# PonyProg_ver1.net
KiCad netlist of a schematic drawn in EAGLE
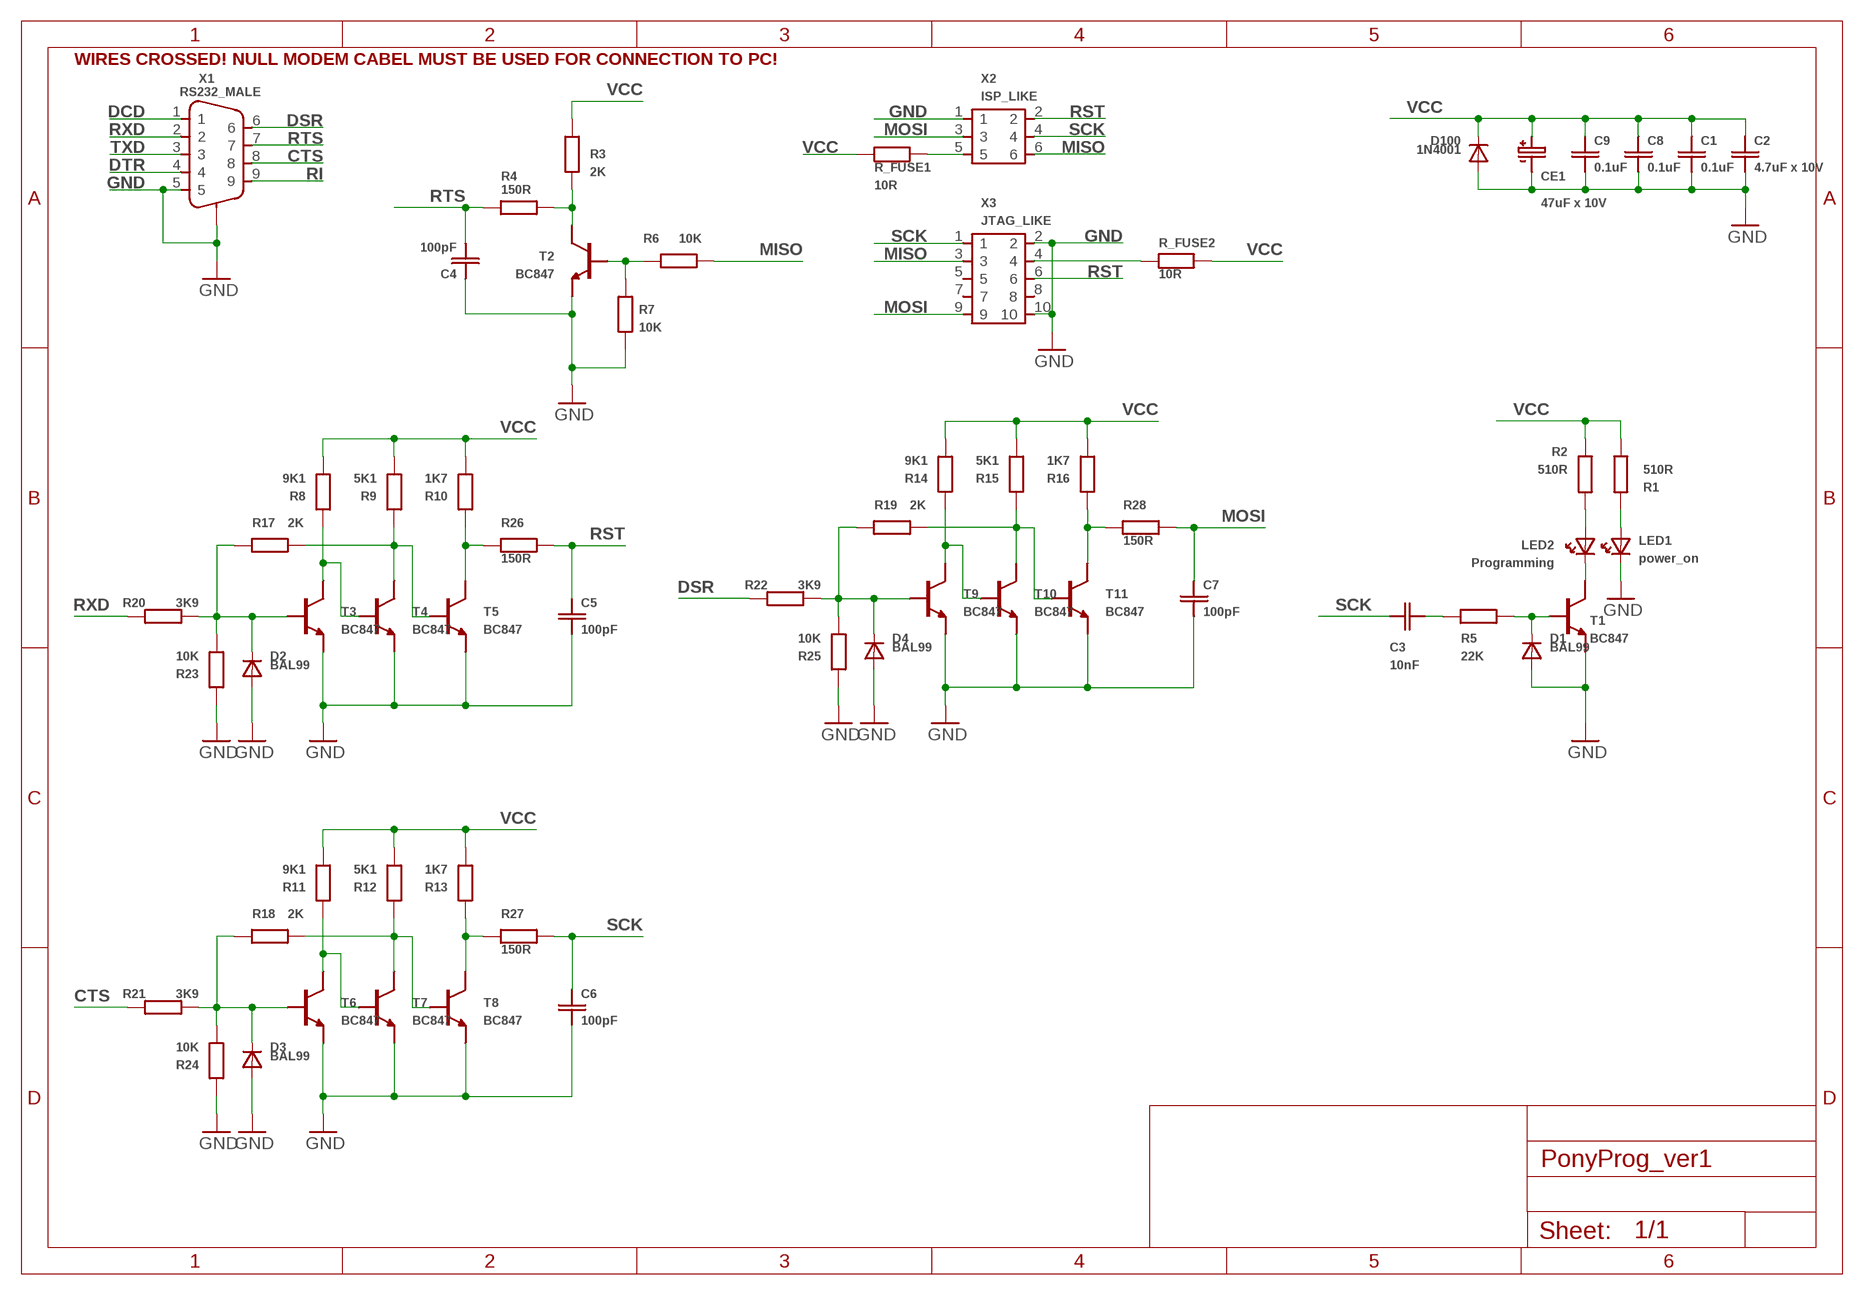
[diagram p0: schematic, sheet 1]

(export (version "E")
  (design (tool "Eeschema 10.0.6"))
  (components
    (comp (ref "C1")
      (value "0.1uF")
      (footprint "eagle-import:RSMD_0805")
      (libsource (lib "eagle-import") (part "CSMD_0805"))
    )
    (comp (ref "C2")
      (value "4.7uF x 10V")
      (footprint "eagle-import:RSMD_1206")
      (libsource (lib "eagle-import") (part "CSMD_1206"))
    )
    (comp (ref "C3")
      (value "10nF")
      (footprint "eagle-import:RSMD_0805")
      (libsource (lib "eagle-import") (part "CSMD_0805"))
    )
    (comp (ref "C4")
      (value "100pF")
      (footprint "eagle-import:RSMD_0805")
      (libsource (lib "eagle-import") (part "CSMD_0805"))
    )
    (comp (ref "C5")
      (value "100pF")
      (footprint "eagle-import:RSMD_0805")
      (libsource (lib "eagle-import") (part "CSMD_0805"))
    )
    (comp (ref "C6")
      (value "100pF")
      (footprint "eagle-import:RSMD_0805")
      (libsource (lib "eagle-import") (part "CSMD_0805"))
    )
    (comp (ref "C7")
      (value "100pF")
      (footprint "eagle-import:RSMD_0805")
      (libsource (lib "eagle-import") (part "CSMD_0805"))
    )
    (comp (ref "C8")
      (value "0.1uF")
      (footprint "eagle-import:RSMD_0805")
      (libsource (lib "eagle-import") (part "CSMD_0805"))
    )
    (comp (ref "C9")
      (value "0.1uF")
      (footprint "eagle-import:RSMD_0805")
      (libsource (lib "eagle-import") (part "CSMD_0805"))
    )
    (comp (ref "CE1")
      (value "47uF x 10V")
      (footprint "eagle-import:CE_6.3MM")
      (libsource (lib "eagle-import") (part "CE6.3MM"))
    )
    (comp (ref "D1")
      (value "BAL99")
      (footprint "eagle-import:SOT23_SMALL_PADS")
      (libsource (lib "eagle-import") (part "BAL99SOT23_SMALL_PADS"))
    )
    (comp (ref "D2")
      (value "BAL99")
      (footprint "eagle-import:SOT23_SMALL_PADS")
      (libsource (lib "eagle-import") (part "BAL99SOT23_SMALL_PADS"))
    )
    (comp (ref "D3")
      (value "BAL99")
      (footprint "eagle-import:SOT23_SMALL_PADS")
      (libsource (lib "eagle-import") (part "BAL99SOT23_SMALL_PADS"))
    )
    (comp (ref "D4")
      (value "BAL99")
      (footprint "eagle-import:SOT23_SMALL_PADS")
      (libsource (lib "eagle-import") (part "BAL99SOT23_SMALL_PADS"))
    )
    (comp (ref "D100")
      (value "1N4001")
      (footprint "eagle-import:DO-41_20MM")
      (libsource (lib "eagle-import") (part "1N4001DO-41_20MM"))
    )
    (comp (ref "LED1")
      (value "power_on")
      (footprint "eagle-import:LED3MM")
      (libsource (lib "eagle-import") (part "LED3MM"))
    )
    (comp (ref "LED2")
      (value "Programming")
      (footprint "eagle-import:LED3MM")
      (libsource (lib "eagle-import") (part "LED3MM"))
    )
    (comp (ref "R1")
      (value "510R")
      (footprint "eagle-import:RSMD_0805")
      (libsource (lib "eagle-import") (part "RSMD_0805"))
    )
    (comp (ref "R2")
      (value "510R")
      (footprint "eagle-import:RSMD_0805")
      (libsource (lib "eagle-import") (part "RSMD_0805"))
    )
    (comp (ref "R3")
      (value "2K")
      (footprint "eagle-import:RSMD_1206")
      (libsource (lib "eagle-import") (part "RSMD_1206"))
    )
    (comp (ref "R4")
      (value "150R")
      (footprint "eagle-import:RSMD_0805")
      (libsource (lib "eagle-import") (part "RSMD_0805"))
    )
    (comp (ref "R5")
      (value "22K")
      (footprint "eagle-import:RSMD_0805")
      (libsource (lib "eagle-import") (part "RSMD_0805"))
    )
    (comp (ref "R6")
      (value "10K")
      (footprint "eagle-import:RSMD_1206")
      (libsource (lib "eagle-import") (part "RSMD_1206"))
    )
    (comp (ref "R7")
      (value "10K")
      (footprint "eagle-import:RSMD_0805")
      (libsource (lib "eagle-import") (part "RSMD_0805"))
    )
    (comp (ref "R8")
      (value "9K1")
      (footprint "eagle-import:RSMD_1206")
      (libsource (lib "eagle-import") (part "RSMD_1206"))
    )
    (comp (ref "R9")
      (value "5K1")
      (footprint "eagle-import:RSMD_0805")
      (libsource (lib "eagle-import") (part "RSMD_0805"))
    )
    (comp (ref "R10")
      (value "1K7")
      (footprint "eagle-import:RSMD_0805")
      (libsource (lib "eagle-import") (part "RSMD_0805"))
    )
    (comp (ref "R11")
      (value "9K1")
      (footprint "eagle-import:RSMD_1206")
      (libsource (lib "eagle-import") (part "RSMD_1206"))
    )
    (comp (ref "R12")
      (value "5K1")
      (footprint "eagle-import:RSMD_0805")
      (libsource (lib "eagle-import") (part "RSMD_0805"))
    )
    (comp (ref "R13")
      (value "1K7")
      (footprint "eagle-import:RSMD_0805")
      (libsource (lib "eagle-import") (part "RSMD_0805"))
    )
    (comp (ref "R14")
      (value "9K1")
      (footprint "eagle-import:RSMD_1206")
      (libsource (lib "eagle-import") (part "RSMD_1206"))
    )
    (comp (ref "R15")
      (value "5K1")
      (footprint "eagle-import:RSMD_0805")
      (libsource (lib "eagle-import") (part "RSMD_0805"))
    )
    (comp (ref "R16")
      (value "1K7")
      (footprint "eagle-import:RSMD_0805")
      (libsource (lib "eagle-import") (part "RSMD_0805"))
    )
    (comp (ref "R17")
      (value "2K")
      (footprint "eagle-import:RSMD_0805")
      (libsource (lib "eagle-import") (part "RSMD_0805"))
    )
    (comp (ref "R18")
      (value "2K")
      (footprint "eagle-import:RSMD_0805")
      (libsource (lib "eagle-import") (part "RSMD_0805"))
    )
    (comp (ref "R19")
      (value "2K")
      (footprint "eagle-import:RSMD_0805")
      (libsource (lib "eagle-import") (part "RSMD_0805"))
    )
    (comp (ref "R20")
      (value "3K9")
      (footprint "eagle-import:RSMD_0805")
      (libsource (lib "eagle-import") (part "RSMD_0805"))
    )
    (comp (ref "R21")
      (value "3K9")
      (footprint "eagle-import:RSMD_0805")
      (libsource (lib "eagle-import") (part "RSMD_0805"))
    )
    (comp (ref "R22")
      (value "3K9")
      (footprint "eagle-import:RSMD_0805")
      (libsource (lib "eagle-import") (part "RSMD_0805"))
    )
    (comp (ref "R23")
      (value "10K")
      (footprint "eagle-import:RSMD_0805")
      (libsource (lib "eagle-import") (part "RSMD_0805"))
    )
    (comp (ref "R24")
      (value "10K")
      (footprint "eagle-import:RSMD_0805")
      (libsource (lib "eagle-import") (part "RSMD_0805"))
    )
    (comp (ref "R25")
      (value "10K")
      (footprint "eagle-import:RSMD_0805")
      (libsource (lib "eagle-import") (part "RSMD_0805"))
    )
    (comp (ref "R26")
      (value "150R")
      (footprint "eagle-import:RSMD_0805")
      (libsource (lib "eagle-import") (part "RSMD_0805"))
    )
    (comp (ref "R27")
      (value "150R")
      (footprint "eagle-import:RSMD_0805")
      (libsource (lib "eagle-import") (part "RSMD_0805"))
    )
    (comp (ref "R28")
      (value "150R")
      (footprint "eagle-import:RSMD_0805")
      (libsource (lib "eagle-import") (part "RSMD_0805"))
    )
    (comp (ref "R_FUSE1")
      (value "10R")
      (footprint "eagle-import:R0207")
      (libsource (lib "eagle-import") (part "R0207"))
    )
    (comp (ref "R_FUSE2")
      (value "10R")
      (footprint "eagle-import:R0207")
      (libsource (lib "eagle-import") (part "R0207"))
    )
    (comp (ref "T1")
      (value "BC847")
      (footprint "eagle-import:SOT23_SMALL_PADS")
      (libsource (lib "eagle-import") (part "BC847SOT23_SMALL_PADS"))
    )
    (comp (ref "T2")
      (value "BC847")
      (footprint "eagle-import:SOT23_SMALL_PADS")
      (libsource (lib "eagle-import") (part "BC847SOT23_SMALL_PADS"))
    )
    (comp (ref "T3")
      (value "BC847")
      (footprint "eagle-import:SOT23_SMALL_PADS")
      (libsource (lib "eagle-import") (part "BC847SOT23_SMALL_PADS"))
    )
    (comp (ref "T4")
      (value "BC847")
      (footprint "eagle-import:SOT23_SMALL_PADS")
      (libsource (lib "eagle-import") (part "BC847SOT23_SMALL_PADS"))
    )
    (comp (ref "T5")
      (value "BC847")
      (footprint "eagle-import:SOT23_SMALL_PADS")
      (libsource (lib "eagle-import") (part "BC847SOT23_SMALL_PADS"))
    )
    (comp (ref "T6")
      (value "BC847")
      (footprint "eagle-import:SOT23_SMALL_PADS")
      (libsource (lib "eagle-import") (part "BC847SOT23_SMALL_PADS"))
    )
    (comp (ref "T7")
      (value "BC847")
      (footprint "eagle-import:SOT23_SMALL_PADS")
      (libsource (lib "eagle-import") (part "BC847SOT23_SMALL_PADS"))
    )
    (comp (ref "T8")
      (value "BC847")
      (footprint "eagle-import:SOT23_SMALL_PADS")
      (libsource (lib "eagle-import") (part "BC847SOT23_SMALL_PADS"))
    )
    (comp (ref "T9")
      (value "BC847")
      (footprint "eagle-import:SOT23_SMALL_PADS")
      (libsource (lib "eagle-import") (part "BC847SOT23_SMALL_PADS"))
    )
    (comp (ref "T10")
      (value "BC847")
      (footprint "eagle-import:SOT23_SMALL_PADS")
      (libsource (lib "eagle-import") (part "BC847SOT23_SMALL_PADS"))
    )
    (comp (ref "T11")
      (value "BC847")
      (footprint "eagle-import:SOT23_SMALL_PADS")
      (libsource (lib "eagle-import") (part "BC847SOT23_SMALL_PADS"))
    )
    (comp (ref "X1")
      (value "RS232_MALE")
      (footprint "eagle-import:DSUB9_RA_MALE")
      (libsource (lib "eagle-import") (part "DSUB9_MALE"))
    )
    (comp (ref "X2")
      (value "ISP_LIKE")
      (footprint "eagle-import:PIN2X3_2.54MM")
      (libsource (lib "eagle-import") (part "PIN2X3_2.54MM"))
    )
    (comp (ref "X3")
      (value "JTAG_LIKE")
      (footprint "eagle-import:PIN2X5_2.54MM")
      (libsource (lib "eagle-import") (part "PIN2X5_2.54MM"))
    )
  )
  (nets
    (net (code "1") (name "/CTS") (class "Default")
      (node (ref "R21") (pin "PAD_1") (pinfunction "PIN1_PAD_1") (pintype "passive"))
      (node (ref "X1") (pin "8") (pinfunction "8_8") (pintype "bidirectional"))
    )
    (net (code "2") (name "/DCD") (class "Default")
      (node (ref "X1") (pin "1") (pinfunction "1_1") (pintype "bidirectional"))
    )
    (net (code "3") (name "/DSR") (class "Default")
      (node (ref "R22") (pin "PAD_1") (pinfunction "PIN1_PAD_1") (pintype "passive"))
      (node (ref "X1") (pin "6") (pinfunction "6_6") (pintype "bidirectional"))
    )
    (net (code "4") (name "/DTR") (class "Default")
      (node (ref "X1") (pin "4") (pinfunction "4_4") (pintype "bidirectional"))
    )
    (net (code "5") (name "/MISO") (class "Default")
      (node (ref "R6") (pin "PAD_1") (pinfunction "PIN1_PAD_1") (pintype "passive"))
      (node (ref "X2") (pin "6") (pinfunction "6_6") (pintype "bidirectional"))
      (node (ref "X3") (pin "3") (pinfunction "3_3") (pintype "bidirectional"))
    )
    (net (code "6") (name "/MOSI") (class "Default")
      (node (ref "C7") (pin "PAD_1") (pinfunction "PIN1_PAD_1") (pintype "bidirectional"))
      (node (ref "R28") (pin "PAD_0") (pinfunction "PIN0_PAD_0") (pintype "passive"))
      (node (ref "X2") (pin "3") (pinfunction "3_3") (pintype "bidirectional"))
      (node (ref "X3") (pin "9") (pinfunction "9_9") (pintype "bidirectional"))
    )
    (net (code "7") (name "/RI") (class "Default")
      (node (ref "X1") (pin "9") (pinfunction "9_9") (pintype "bidirectional"))
    )
    (net (code "8") (name "/RST") (class "Default")
      (node (ref "C5") (pin "PAD_1") (pinfunction "PIN1_PAD_1") (pintype "bidirectional"))
      (node (ref "R26") (pin "PAD_0") (pinfunction "PIN0_PAD_0") (pintype "passive"))
      (node (ref "X2") (pin "2") (pinfunction "2_2") (pintype "bidirectional"))
      (node (ref "X3") (pin "6") (pinfunction "6_6") (pintype "bidirectional"))
    )
    (net (code "9") (name "/RTS") (class "Default")
      (node (ref "C4") (pin "PAD_0") (pinfunction "PIN0_PAD_0") (pintype "bidirectional"))
      (node (ref "R4") (pin "PAD_1") (pinfunction "PIN1_PAD_1") (pintype "passive"))
      (node (ref "X1") (pin "7") (pinfunction "7_7") (pintype "bidirectional"))
    )
    (net (code "10") (name "/RXD") (class "Default")
      (node (ref "R20") (pin "PAD_1") (pinfunction "PIN1_PAD_1") (pintype "passive"))
      (node (ref "X1") (pin "2") (pinfunction "2_2") (pintype "bidirectional"))
    )
    (net (code "11") (name "/SCK") (class "Default")
      (node (ref "C3") (pin "PAD_1") (pinfunction "PIN1_PAD_1") (pintype "bidirectional"))
      (node (ref "C6") (pin "PAD_1") (pinfunction "PIN1_PAD_1") (pintype "bidirectional"))
      (node (ref "R27") (pin "PAD_0") (pinfunction "PIN0_PAD_0") (pintype "passive"))
      (node (ref "X2") (pin "4") (pinfunction "4_4") (pintype "bidirectional"))
      (node (ref "X3") (pin "1") (pinfunction "1_1") (pintype "bidirectional"))
    )
    (net (code "12") (name "/TXD") (class "Default")
      (node (ref "X1") (pin "3") (pinfunction "3_3") (pintype "bidirectional"))
    )
    (net (code "13") (name "/VCC") (class "Default")
      (node (ref "C1") (pin "PAD_1") (pinfunction "PIN1_PAD_1") (pintype "bidirectional"))
      (node (ref "C2") (pin "PAD_1") (pinfunction "PIN1_PAD_1") (pintype "bidirectional"))
      (node (ref "C8") (pin "PAD_1") (pinfunction "PIN1_PAD_1") (pintype "bidirectional"))
      (node (ref "C9") (pin "PAD_1") (pinfunction "PIN1_PAD_1") (pintype "bidirectional"))
      (node (ref "CE1") (pin "+") (pinfunction "+_+") (pintype "bidirectional"))
      (node (ref "D100") (pin "CATHODE") (pinfunction "CATHODE_CATHODE") (pintype "passive"))
      (node (ref "R1") (pin "PAD_0") (pinfunction "PIN0_PAD_0") (pintype "passive"))
      (node (ref "R10") (pin "PAD_0") (pinfunction "PIN0_PAD_0") (pintype "passive"))
      (node (ref "R11") (pin "PAD_0") (pinfunction "PIN0_PAD_0") (pintype "passive"))
      (node (ref "R12") (pin "PAD_0") (pinfunction "PIN0_PAD_0") (pintype "passive"))
      (node (ref "R13") (pin "PAD_0") (pinfunction "PIN0_PAD_0") (pintype "passive"))
      (node (ref "R14") (pin "PAD_0") (pinfunction "PIN0_PAD_0") (pintype "passive"))
      (node (ref "R15") (pin "PAD_0") (pinfunction "PIN0_PAD_0") (pintype "passive"))
      (node (ref "R16") (pin "PAD_0") (pinfunction "PIN0_PAD_0") (pintype "passive"))
      (node (ref "R2") (pin "PAD_0") (pinfunction "PIN0_PAD_0") (pintype "passive"))
      (node (ref "R3") (pin "PAD_1") (pinfunction "PIN1_PAD_1") (pintype "passive"))
      (node (ref "R8") (pin "PAD_0") (pinfunction "PIN0_PAD_0") (pintype "passive"))
      (node (ref "R9") (pin "PAD_0") (pinfunction "PIN0_PAD_0") (pintype "passive"))
      (node (ref "R_FUSE1") (pin "PAD_0") (pinfunction "PIN0_PAD_0") (pintype "passive"))
      (node (ref "R_FUSE2") (pin "PAD1") (pinfunction "PIN1_PAD1") (pintype "passive"))
    )
    (net (code "14") (name "GND") (class "Default")
      (node (ref "C1") (pin "PAD_0") (pinfunction "PIN0_PAD_0") (pintype "bidirectional"))
      (node (ref "C2") (pin "PAD_0") (pinfunction "PIN0_PAD_0") (pintype "bidirectional"))
      (node (ref "C4") (pin "PAD_1") (pinfunction "PIN1_PAD_1") (pintype "bidirectional"))
      (node (ref "C5") (pin "PAD_0") (pinfunction "PIN0_PAD_0") (pintype "bidirectional"))
      (node (ref "C6") (pin "PAD_0") (pinfunction "PIN0_PAD_0") (pintype "bidirectional"))
      (node (ref "C7") (pin "PAD_0") (pinfunction "PIN0_PAD_0") (pintype "bidirectional"))
      (node (ref "C8") (pin "PAD_0") (pinfunction "PIN0_PAD_0") (pintype "bidirectional"))
      (node (ref "C9") (pin "PAD_0") (pinfunction "PIN0_PAD_0") (pintype "bidirectional"))
      (node (ref "CE1") (pin "-") (pinfunction "-_-") (pintype "bidirectional"))
      (node (ref "D1") (pin "3") (pinfunction "ANODE_3") (pintype "passive"))
      (node (ref "D100") (pin "ANODE") (pinfunction "ANODE_ANODE") (pintype "passive"))
      (node (ref "D2") (pin "3") (pinfunction "ANODE_3") (pintype "passive"))
      (node (ref "D3") (pin "3") (pinfunction "ANODE_3") (pintype "passive"))
      (node (ref "D4") (pin "3") (pinfunction "ANODE_3") (pintype "passive"))
      (node (ref "LED1") (pin "CATHODE") (pinfunction "CATHODE_CATHODE") (pintype "passive"))
      (node (ref "R23") (pin "PAD_1") (pinfunction "PIN1_PAD_1") (pintype "passive"))
      (node (ref "R24") (pin "PAD_1") (pinfunction "PIN1_PAD_1") (pintype "passive"))
      (node (ref "R25") (pin "PAD_1") (pinfunction "PIN1_PAD_1") (pintype "passive"))
      (node (ref "R7") (pin "PAD_0") (pinfunction "PIN0_PAD_0") (pintype "passive"))
      (node (ref "T1") (pin "2") (pinfunction "E_2") (pintype "bidirectional"))
      (node (ref "T10") (pin "2") (pinfunction "E_2") (pintype "bidirectional"))
      (node (ref "T11") (pin "2") (pinfunction "E_2") (pintype "bidirectional"))
      (node (ref "T2") (pin "2") (pinfunction "E_2") (pintype "bidirectional"))
      (node (ref "T3") (pin "2") (pinfunction "E_2") (pintype "bidirectional"))
      (node (ref "T4") (pin "2") (pinfunction "E_2") (pintype "bidirectional"))
      (node (ref "T5") (pin "2") (pinfunction "E_2") (pintype "bidirectional"))
      (node (ref "T6") (pin "2") (pinfunction "E_2") (pintype "bidirectional"))
      (node (ref "T7") (pin "2") (pinfunction "E_2") (pintype "bidirectional"))
      (node (ref "T8") (pin "2") (pinfunction "E_2") (pintype "bidirectional"))
      (node (ref "T9") (pin "2") (pinfunction "E_2") (pintype "bidirectional"))
      (node (ref "X1") (pin "5") (pinfunction "5_5") (pintype "bidirectional"))
      (node (ref "X1") (pin "PACKAGE1") (pinfunction "PACKAGE1_PACKAGE1") (pintype "bidirectional"))
      (node (ref "X1") (pin "PACKAGE2") (pinfunction "PACKAGE1_PACKAGE2") (pintype "bidirectional"))
      (node (ref "X2") (pin "1") (pinfunction "1_1") (pintype "bidirectional"))
      (node (ref "X3") (pin "10") (pinfunction "10_10") (pintype "bidirectional"))
      (node (ref "X3") (pin "2") (pinfunction "2_2") (pintype "bidirectional"))
    )
    (net (code "15") (name "Net-(C3-PIN0)") (class "Default")
      (node (ref "C3") (pin "PAD_0") (pinfunction "PIN0_PAD_0") (pintype "bidirectional"))
      (node (ref "R5") (pin "PAD_0") (pinfunction "PIN0_PAD_0") (pintype "passive"))
    )
    (net (code "16") (name "Net-(D1-CATHODE)") (class "Default")
      (node (ref "D1") (pin "2") (pinfunction "CATHODE_2") (pintype "passive"))
      (node (ref "R5") (pin "PAD_1") (pinfunction "PIN1_PAD_1") (pintype "passive"))
      (node (ref "T1") (pin "1") (pinfunction "B_1") (pintype "bidirectional"))
    )
    (net (code "17") (name "Net-(D2-CATHODE)") (class "Default")
      (node (ref "D2") (pin "2") (pinfunction "CATHODE_2") (pintype "passive"))
      (node (ref "R17") (pin "PAD_1") (pinfunction "PIN1_PAD_1") (pintype "passive"))
      (node (ref "R20") (pin "PAD_0") (pinfunction "PIN0_PAD_0") (pintype "passive"))
      (node (ref "R23") (pin "PAD_0") (pinfunction "PIN0_PAD_0") (pintype "passive"))
      (node (ref "T3") (pin "1") (pinfunction "B_1") (pintype "bidirectional"))
    )
    (net (code "18") (name "Net-(D3-CATHODE)") (class "Default")
      (node (ref "D3") (pin "2") (pinfunction "CATHODE_2") (pintype "passive"))
      (node (ref "R18") (pin "PAD_1") (pinfunction "PIN1_PAD_1") (pintype "passive"))
      (node (ref "R21") (pin "PAD_0") (pinfunction "PIN0_PAD_0") (pintype "passive"))
      (node (ref "R24") (pin "PAD_0") (pinfunction "PIN0_PAD_0") (pintype "passive"))
      (node (ref "T6") (pin "1") (pinfunction "B_1") (pintype "bidirectional"))
    )
    (net (code "19") (name "Net-(D4-CATHODE)") (class "Default")
      (node (ref "D4") (pin "2") (pinfunction "CATHODE_2") (pintype "passive"))
      (node (ref "R19") (pin "PAD_1") (pinfunction "PIN1_PAD_1") (pintype "passive"))
      (node (ref "R22") (pin "PAD_0") (pinfunction "PIN0_PAD_0") (pintype "passive"))
      (node (ref "R25") (pin "PAD_0") (pinfunction "PIN0_PAD_0") (pintype "passive"))
      (node (ref "T9") (pin "1") (pinfunction "B_1") (pintype "bidirectional"))
    )
    (net (code "20") (name "Net-(R1-PIN1)") (class "Default")
      (node (ref "LED1") (pin "ANODE") (pinfunction "ANODE_ANODE") (pintype "passive"))
      (node (ref "R1") (pin "PAD_1") (pinfunction "PIN1_PAD_1") (pintype "passive"))
    )
    (net (code "21") (name "Net-(R2-PIN1)") (class "Default")
      (node (ref "LED2") (pin "ANODE") (pinfunction "ANODE_ANODE") (pintype "passive"))
      (node (ref "R2") (pin "PAD_1") (pinfunction "PIN1_PAD_1") (pintype "passive"))
    )
    (net (code "22") (name "Net-(R3-PIN0)") (class "Default")
      (node (ref "R3") (pin "PAD_0") (pinfunction "PIN0_PAD_0") (pintype "passive"))
      (node (ref "R4") (pin "PAD_0") (pinfunction "PIN0_PAD_0") (pintype "passive"))
      (node (ref "T2") (pin "3") (pinfunction "C_3") (pintype "bidirectional"))
    )
    (net (code "23") (name "Net-(R6-PIN0)") (class "Default")
      (node (ref "R6") (pin "PAD_0") (pinfunction "PIN0_PAD_0") (pintype "passive"))
      (node (ref "R7") (pin "PAD_1") (pinfunction "PIN1_PAD_1") (pintype "passive"))
      (node (ref "T2") (pin "1") (pinfunction "B_1") (pintype "bidirectional"))
    )
    (net (code "24") (name "Net-(R8-PIN1)") (class "Default")
      (node (ref "R8") (pin "PAD_1") (pinfunction "PIN1_PAD_1") (pintype "passive"))
      (node (ref "T3") (pin "3") (pinfunction "C_3") (pintype "bidirectional"))
      (node (ref "T4") (pin "1") (pinfunction "B_1") (pintype "bidirectional"))
    )
    (net (code "25") (name "Net-(R10-PIN1)") (class "Default")
      (node (ref "R10") (pin "PAD_1") (pinfunction "PIN1_PAD_1") (pintype "passive"))
      (node (ref "R26") (pin "PAD_1") (pinfunction "PIN1_PAD_1") (pintype "passive"))
      (node (ref "T5") (pin "3") (pinfunction "C_3") (pintype "bidirectional"))
    )
    (net (code "26") (name "Net-(R11-PIN1)") (class "Default")
      (node (ref "R11") (pin "PAD_1") (pinfunction "PIN1_PAD_1") (pintype "passive"))
      (node (ref "T6") (pin "3") (pinfunction "C_3") (pintype "bidirectional"))
      (node (ref "T7") (pin "1") (pinfunction "B_1") (pintype "bidirectional"))
    )
    (net (code "27") (name "Net-(R12-PIN1)") (class "Default")
      (node (ref "R12") (pin "PAD_1") (pinfunction "PIN1_PAD_1") (pintype "passive"))
      (node (ref "R18") (pin "PAD_0") (pinfunction "PIN0_PAD_0") (pintype "passive"))
      (node (ref "T7") (pin "3") (pinfunction "C_3") (pintype "bidirectional"))
      (node (ref "T8") (pin "1") (pinfunction "B_1") (pintype "bidirectional"))
    )
    (net (code "28") (name "Net-(R13-PIN1)") (class "Default")
      (node (ref "R13") (pin "PAD_1") (pinfunction "PIN1_PAD_1") (pintype "passive"))
      (node (ref "R27") (pin "PAD_1") (pinfunction "PIN1_PAD_1") (pintype "passive"))
      (node (ref "T8") (pin "3") (pinfunction "C_3") (pintype "bidirectional"))
    )
    (net (code "29") (name "Net-(R14-PIN1)") (class "Default")
      (node (ref "R14") (pin "PAD_1") (pinfunction "PIN1_PAD_1") (pintype "passive"))
      (node (ref "T10") (pin "1") (pinfunction "B_1") (pintype "bidirectional"))
      (node (ref "T9") (pin "3") (pinfunction "C_3") (pintype "bidirectional"))
    )
    (net (code "30") (name "Net-(R15-PIN1)") (class "Default")
      (node (ref "R15") (pin "PAD_1") (pinfunction "PIN1_PAD_1") (pintype "passive"))
      (node (ref "R19") (pin "PAD_0") (pinfunction "PIN0_PAD_0") (pintype "passive"))
      (node (ref "T10") (pin "3") (pinfunction "C_3") (pintype "bidirectional"))
      (node (ref "T11") (pin "1") (pinfunction "B_1") (pintype "bidirectional"))
    )
    (net (code "31") (name "Net-(R16-PIN1)") (class "Default")
      (node (ref "R16") (pin "PAD_1") (pinfunction "PIN1_PAD_1") (pintype "passive"))
      (node (ref "R28") (pin "PAD_1") (pinfunction "PIN1_PAD_1") (pintype "passive"))
      (node (ref "T11") (pin "3") (pinfunction "C_3") (pintype "bidirectional"))
    )
    (net (code "32") (name "Net-(R17-PIN0)") (class "Default")
      (node (ref "R17") (pin "PAD_0") (pinfunction "PIN0_PAD_0") (pintype "passive"))
      (node (ref "R9") (pin "PAD_1") (pinfunction "PIN1_PAD_1") (pintype "passive"))
      (node (ref "T4") (pin "3") (pinfunction "C_3") (pintype "bidirectional"))
      (node (ref "T5") (pin "1") (pinfunction "B_1") (pintype "bidirectional"))
    )
    (net (code "33") (name "Net-(R_FUSE1-PIN1)") (class "Default")
      (node (ref "R_FUSE1") (pin "PAD1") (pinfunction "PIN1_PAD1") (pintype "passive"))
      (node (ref "X2") (pin "5") (pinfunction "5_5") (pintype "bidirectional"))
    )
    (net (code "34") (name "Net-(R_FUSE2-PIN0)") (class "Default")
      (node (ref "R_FUSE2") (pin "PAD_0") (pinfunction "PIN0_PAD_0") (pintype "passive"))
      (node (ref "X3") (pin "4") (pinfunction "4_4") (pintype "bidirectional"))
    )
    (net (code "35") (name "Net-(T1-C)") (class "Default")
      (node (ref "LED2") (pin "CATHODE") (pinfunction "CATHODE_CATHODE") (pintype "passive"))
      (node (ref "T1") (pin "3") (pinfunction "C_3") (pintype "bidirectional"))
    )
    (net (code "36") (name "unconnected-(X3-Pad5)") (class "Default")
      (node (ref "X3") (pin "5") (pinfunction "5_5") (pintype "bidirectional"))
    )
    (net (code "37") (name "unconnected-(X3-Pad7)") (class "Default")
      (node (ref "X3") (pin "7") (pinfunction "7_7") (pintype "bidirectional"))
    )
    (net (code "38") (name "unconnected-(X3-Pad8)") (class "Default")
      (node (ref "X3") (pin "8") (pinfunction "8_8") (pintype "bidirectional"))
    )
  )
)
